# drake-1.net
KiCad netlist of a schematic drawn in Altium Designer
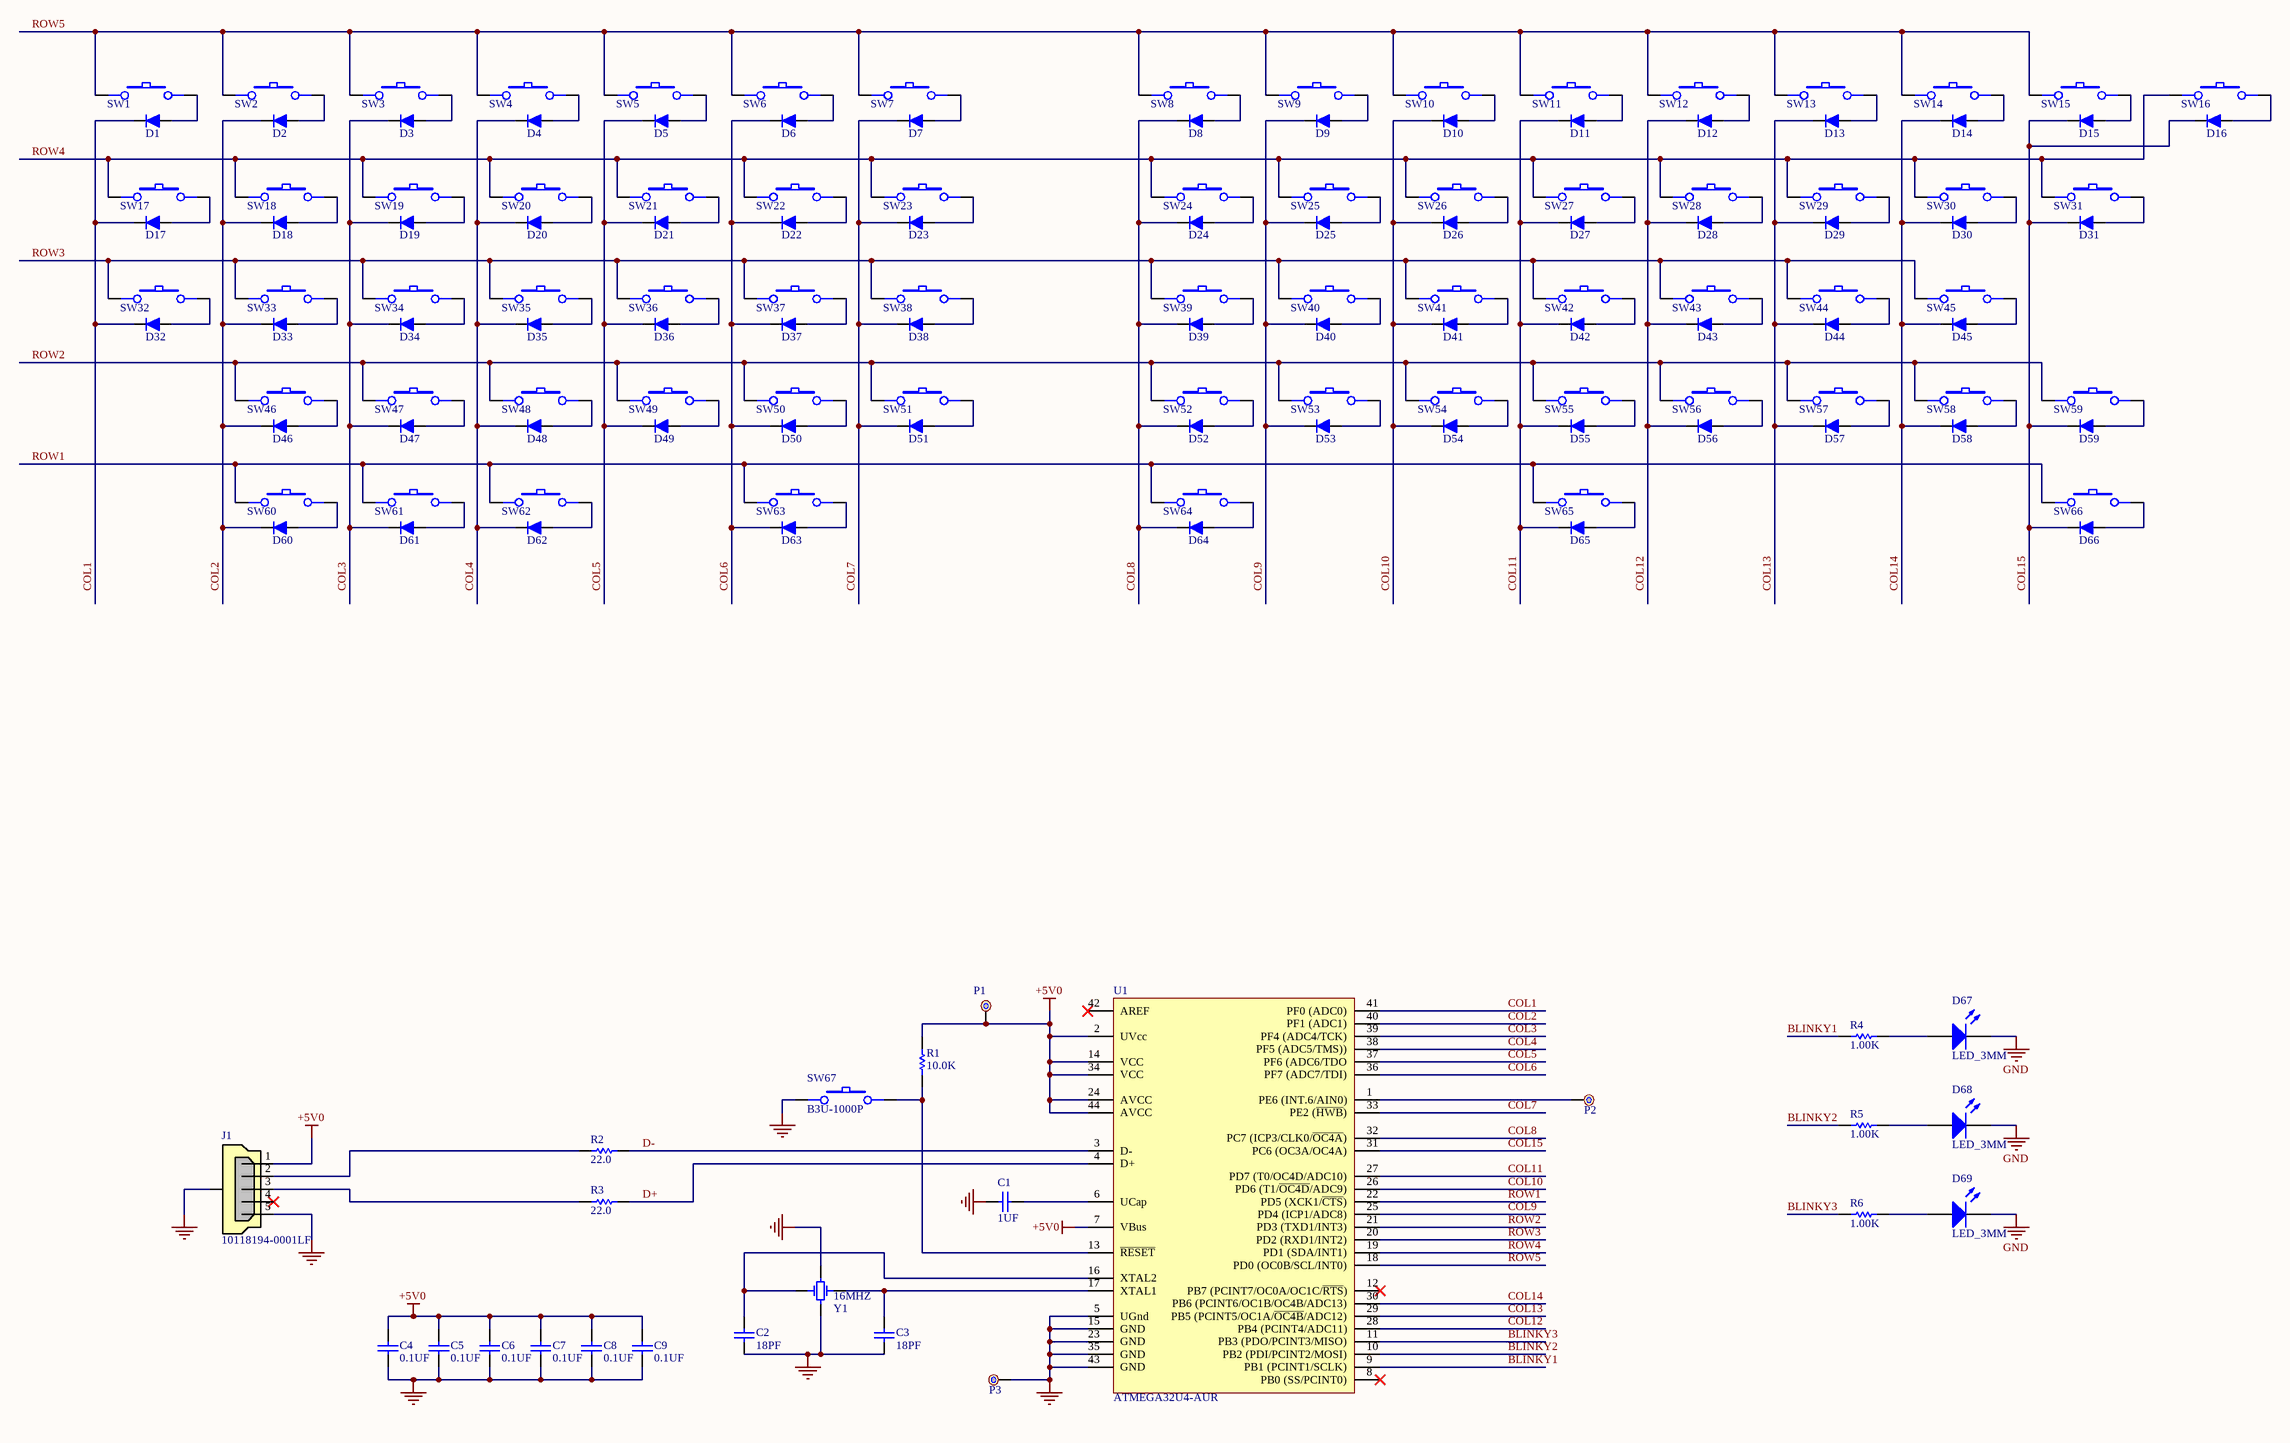
[diagram p0: drake-1.SchDoc]

(export (version "E")
  (design (tool "Eeschema 10.0.6"))
  (components
    (comp (ref "C1")
      (value "1UF")
      (footprint "CAPC2012X14N")
      (description "=Reference")
      (fields
        (field (name "MANUFACTURER") "Murata")
        (field (name "MANUFACTURER PART NUMBER") "GRM21BR71A105KA01L")
      )
      (libsource (lib "Altium_Library") (part "Capacitor-NP"))
    )
    (comp (ref "C2")
      (value "18PF")
      (footprint "CAPC1005X06N")
      (description "=Reference")
      (fields
        (field (name "MANUFACTURER") "Murata")
        (field (name "MANUFACTURER PART NUMBER") "GRM1555C1H180JA01D")
      )
      (libsource (lib "Altium_Library") (part "Capacitor-NP"))
    )
    (comp (ref "C3")
      (value "18PF")
      (footprint "CAPC1005X06N")
      (description "=Reference")
      (fields
        (field (name "MANUFACTURER") "Murata")
        (field (name "MANUFACTURER PART NUMBER") "GRM1555C1H180JA01D")
      )
      (libsource (lib "Altium_Library") (part "Capacitor-NP"))
    )
    (comp (ref "C4")
      (value "0.1UF")
      (footprint "CAPC1005X06N")
      (description "=Reference")
      (fields
        (field (name "MANUFACTURER") "Murata")
        (field (name "MANUFACTURER PART NUMBER") "GRM155R71C104KA88D")
      )
      (libsource (lib "Altium_Library") (part "Capacitor-NP"))
    )
    (comp (ref "C5")
      (value "0.1UF")
      (footprint "CAPC1005X06N")
      (description "=Reference")
      (fields
        (field (name "MANUFACTURER") "Murata")
        (field (name "MANUFACTURER PART NUMBER") "GRM155R71C104KA88D")
      )
      (libsource (lib "Altium_Library") (part "Capacitor-NP"))
    )
    (comp (ref "C6")
      (value "0.1UF")
      (footprint "CAPC1005X06N")
      (description "=Reference")
      (fields
        (field (name "MANUFACTURER") "Murata")
        (field (name "MANUFACTURER PART NUMBER") "GRM155R71C104KA88D")
      )
      (libsource (lib "Altium_Library") (part "Capacitor-NP"))
    )
    (comp (ref "C7")
      (value "0.1UF")
      (footprint "CAPC1005X06N")
      (description "=Reference")
      (fields
        (field (name "MANUFACTURER") "Murata")
        (field (name "MANUFACTURER PART NUMBER") "GRM155R71C104KA88D")
      )
      (libsource (lib "Altium_Library") (part "Capacitor-NP"))
    )
    (comp (ref "C8")
      (value "0.1UF")
      (footprint "CAPC1005X06N")
      (description "=Reference")
      (fields
        (field (name "MANUFACTURER") "Murata")
        (field (name "MANUFACTURER PART NUMBER") "GRM155R71C104KA88D")
      )
      (libsource (lib "Altium_Library") (part "Capacitor-NP"))
    )
    (comp (ref "C9")
      (value "0.1UF")
      (footprint "CAPC1005X06N")
      (description "=Reference")
      (fields
        (field (name "MANUFACTURER") "Murata")
        (field (name "MANUFACTURER PART NUMBER") "GRM155R71C104KA88D")
      )
      (libsource (lib "Altium_Library") (part "Capacitor-NP"))
    )
    (comp (ref "D1")
      (value "1N4148WS-7-F")
      (footprint "SOD-323")
      (description "DIODE GEN PURP 75V 150MA SOD323")
      (fields (field (name "MANUFACTURER") "Diodes Inc."))
      (libsource (lib "Schlib1") (part "1N4148WS-7-F"))
    )
    (comp (ref "D2")
      (value "1N4148WS-7-F")
      (footprint "SOD-323")
      (description "DIODE GEN PURP 75V 150MA SOD323")
      (fields (field (name "MANUFACTURER") "Diodes Inc."))
      (libsource (lib "Schlib1") (part "1N4148WS-7-F"))
    )
    (comp (ref "D3")
      (value "1N4148WS-7-F")
      (footprint "SOD-323")
      (description "DIODE GEN PURP 75V 150MA SOD323")
      (fields (field (name "MANUFACTURER") "Diodes Inc."))
      (libsource (lib "Schlib1") (part "1N4148WS-7-F"))
    )
    (comp (ref "D4")
      (value "1N4148WS-7-F")
      (footprint "SOD-323")
      (description "DIODE GEN PURP 75V 150MA SOD323")
      (fields (field (name "MANUFACTURER") "Diodes Inc."))
      (libsource (lib "Schlib1") (part "1N4148WS-7-F"))
    )
    (comp (ref "D5")
      (value "1N4148WS-7-F")
      (footprint "SOD-323")
      (description "DIODE GEN PURP 75V 150MA SOD323")
      (fields (field (name "MANUFACTURER") "Diodes Inc."))
      (libsource (lib "Schlib1") (part "1N4148WS-7-F"))
    )
    (comp (ref "D6")
      (value "1N4148WS-7-F")
      (footprint "SOD-323")
      (description "DIODE GEN PURP 75V 150MA SOD323")
      (fields (field (name "MANUFACTURER") "Diodes Inc."))
      (libsource (lib "Schlib1") (part "1N4148WS-7-F"))
    )
    (comp (ref "D7")
      (value "1N4148WS-7-F")
      (footprint "SOD-323")
      (description "DIODE GEN PURP 75V 150MA SOD323")
      (fields (field (name "MANUFACTURER") "Diodes Inc."))
      (libsource (lib "Schlib1") (part "1N4148WS-7-F"))
    )
    (comp (ref "D8")
      (value "1N4148WS-7-F")
      (footprint "SOD-323")
      (description "DIODE GEN PURP 75V 150MA SOD323")
      (fields (field (name "MANUFACTURER") "Diodes Inc."))
      (libsource (lib "Schlib1") (part "1N4148WS-7-F"))
    )
    (comp (ref "D9")
      (value "1N4148WS-7-F")
      (footprint "SOD-323")
      (description "DIODE GEN PURP 75V 150MA SOD323")
      (fields (field (name "MANUFACTURER") "Diodes Inc."))
      (libsource (lib "Schlib1") (part "1N4148WS-7-F"))
    )
    (comp (ref "D10")
      (value "1N4148WS-7-F")
      (footprint "SOD-323")
      (description "DIODE GEN PURP 75V 150MA SOD323")
      (fields (field (name "MANUFACTURER") "Diodes Inc."))
      (libsource (lib "Schlib1") (part "1N4148WS-7-F"))
    )
    (comp (ref "D11")
      (value "1N4148WS-7-F")
      (footprint "SOD-323")
      (description "DIODE GEN PURP 75V 150MA SOD323")
      (fields (field (name "MANUFACTURER") "Diodes Inc."))
      (libsource (lib "Schlib1") (part "1N4148WS-7-F"))
    )
    (comp (ref "D12")
      (value "1N4148WS-7-F")
      (footprint "SOD-323")
      (description "DIODE GEN PURP 75V 150MA SOD323")
      (fields (field (name "MANUFACTURER") "Diodes Inc."))
      (libsource (lib "Schlib1") (part "1N4148WS-7-F"))
    )
    (comp (ref "D13")
      (value "1N4148WS-7-F")
      (footprint "SOD-323")
      (description "DIODE GEN PURP 75V 150MA SOD323")
      (fields (field (name "MANUFACTURER") "Diodes Inc."))
      (libsource (lib "Schlib1") (part "1N4148WS-7-F"))
    )
    (comp (ref "D14")
      (value "1N4148WS-7-F")
      (footprint "SOD-323")
      (description "DIODE GEN PURP 75V 150MA SOD323")
      (fields (field (name "MANUFACTURER") "Diodes Inc."))
      (libsource (lib "Schlib1") (part "1N4148WS-7-F"))
    )
    (comp (ref "D15")
      (value "1N4148WS-7-F")
      (footprint "SOD-323")
      (description "DIODE GEN PURP 75V 150MA SOD323")
      (fields (field (name "MANUFACTURER") "Diodes Inc."))
      (libsource (lib "Schlib1") (part "1N4148WS-7-F"))
    )
    (comp (ref "D16")
      (value "1N4148WS-7-F")
      (footprint "SOD-323")
      (description "DIODE GEN PURP 75V 150MA SOD323")
      (fields (field (name "MANUFACTURER") "Diodes Inc."))
      (libsource (lib "Schlib1") (part "1N4148WS-7-F"))
    )
    (comp (ref "D17")
      (value "1N4148WS-7-F")
      (footprint "SOD-323")
      (description "DIODE GEN PURP 75V 150MA SOD323")
      (fields (field (name "MANUFACTURER") "Diodes Inc."))
      (libsource (lib "Schlib1") (part "1N4148WS-7-F"))
    )
    (comp (ref "D18")
      (value "1N4148WS-7-F")
      (footprint "SOD-323")
      (description "DIODE GEN PURP 75V 150MA SOD323")
      (fields (field (name "MANUFACTURER") "Diodes Inc."))
      (libsource (lib "Schlib1") (part "1N4148WS-7-F"))
    )
    (comp (ref "D19")
      (value "1N4148WS-7-F")
      (footprint "SOD-323")
      (description "DIODE GEN PURP 75V 150MA SOD323")
      (fields (field (name "MANUFACTURER") "Diodes Inc."))
      (libsource (lib "Schlib1") (part "1N4148WS-7-F"))
    )
    (comp (ref "D20")
      (value "1N4148WS-7-F")
      (footprint "SOD-323")
      (description "DIODE GEN PURP 75V 150MA SOD323")
      (fields (field (name "MANUFACTURER") "Diodes Inc."))
      (libsource (lib "Schlib1") (part "1N4148WS-7-F"))
    )
    (comp (ref "D21")
      (value "1N4148WS-7-F")
      (footprint "SOD-323")
      (description "DIODE GEN PURP 75V 150MA SOD323")
      (fields (field (name "MANUFACTURER") "Diodes Inc."))
      (libsource (lib "Schlib1") (part "1N4148WS-7-F"))
    )
    (comp (ref "D22")
      (value "1N4148WS-7-F")
      (footprint "SOD-323")
      (description "DIODE GEN PURP 75V 150MA SOD323")
      (fields (field (name "MANUFACTURER") "Diodes Inc."))
      (libsource (lib "Schlib1") (part "1N4148WS-7-F"))
    )
    (comp (ref "D23")
      (value "1N4148WS-7-F")
      (footprint "SOD-323")
      (description "DIODE GEN PURP 75V 150MA SOD323")
      (fields (field (name "MANUFACTURER") "Diodes Inc."))
      (libsource (lib "Schlib1") (part "1N4148WS-7-F"))
    )
    (comp (ref "D24")
      (value "1N4148WS-7-F")
      (footprint "SOD-323")
      (description "DIODE GEN PURP 75V 150MA SOD323")
      (fields (field (name "MANUFACTURER") "Diodes Inc."))
      (libsource (lib "Schlib1") (part "1N4148WS-7-F"))
    )
    (comp (ref "D25")
      (value "1N4148WS-7-F")
      (footprint "SOD-323")
      (description "DIODE GEN PURP 75V 150MA SOD323")
      (fields (field (name "MANUFACTURER") "Diodes Inc."))
      (libsource (lib "Schlib1") (part "1N4148WS-7-F"))
    )
    (comp (ref "D26")
      (value "1N4148WS-7-F")
      (footprint "SOD-323")
      (description "DIODE GEN PURP 75V 150MA SOD323")
      (fields (field (name "MANUFACTURER") "Diodes Inc."))
      (libsource (lib "Schlib1") (part "1N4148WS-7-F"))
    )
    (comp (ref "D27")
      (value "1N4148WS-7-F")
      (footprint "SOD-323")
      (description "DIODE GEN PURP 75V 150MA SOD323")
      (fields (field (name "MANUFACTURER") "Diodes Inc."))
      (libsource (lib "Schlib1") (part "1N4148WS-7-F"))
    )
    (comp (ref "D28")
      (value "1N4148WS-7-F")
      (footprint "SOD-323")
      (description "DIODE GEN PURP 75V 150MA SOD323")
      (fields (field (name "MANUFACTURER") "Diodes Inc."))
      (libsource (lib "Schlib1") (part "1N4148WS-7-F"))
    )
    (comp (ref "D29")
      (value "1N4148WS-7-F")
      (footprint "SOD-323")
      (description "DIODE GEN PURP 75V 150MA SOD323")
      (fields (field (name "MANUFACTURER") "Diodes Inc."))
      (libsource (lib "Schlib1") (part "1N4148WS-7-F"))
    )
    (comp (ref "D30")
      (value "1N4148WS-7-F")
      (footprint "SOD-323")
      (description "DIODE GEN PURP 75V 150MA SOD323")
      (fields (field (name "MANUFACTURER") "Diodes Inc."))
      (libsource (lib "Schlib1") (part "1N4148WS-7-F"))
    )
    (comp (ref "D31")
      (value "1N4148WS-7-F")
      (footprint "SOD-323")
      (description "DIODE GEN PURP 75V 150MA SOD323")
      (fields (field (name "MANUFACTURER") "Diodes Inc."))
      (libsource (lib "Schlib1") (part "1N4148WS-7-F"))
    )
    (comp (ref "D32")
      (value "1N4148WS-7-F")
      (footprint "SOD-323")
      (description "DIODE GEN PURP 75V 150MA SOD323")
      (fields (field (name "MANUFACTURER") "Diodes Inc."))
      (libsource (lib "Schlib1") (part "1N4148WS-7-F"))
    )
    (comp (ref "D33")
      (value "1N4148WS-7-F")
      (footprint "SOD-323")
      (description "DIODE GEN PURP 75V 150MA SOD323")
      (fields (field (name "MANUFACTURER") "Diodes Inc."))
      (libsource (lib "Schlib1") (part "1N4148WS-7-F"))
    )
    (comp (ref "D34")
      (value "1N4148WS-7-F")
      (footprint "SOD-323")
      (description "DIODE GEN PURP 75V 150MA SOD323")
      (fields (field (name "MANUFACTURER") "Diodes Inc."))
      (libsource (lib "Schlib1") (part "1N4148WS-7-F"))
    )
    (comp (ref "D35")
      (value "1N4148WS-7-F")
      (footprint "SOD-323")
      (description "DIODE GEN PURP 75V 150MA SOD323")
      (fields (field (name "MANUFACTURER") "Diodes Inc."))
      (libsource (lib "Schlib1") (part "1N4148WS-7-F"))
    )
    (comp (ref "D36")
      (value "1N4148WS-7-F")
      (footprint "SOD-323")
      (description "DIODE GEN PURP 75V 150MA SOD323")
      (fields (field (name "MANUFACTURER") "Diodes Inc."))
      (libsource (lib "Schlib1") (part "1N4148WS-7-F"))
    )
    (comp (ref "D37")
      (value "1N4148WS-7-F")
      (footprint "SOD-323")
      (description "DIODE GEN PURP 75V 150MA SOD323")
      (fields (field (name "MANUFACTURER") "Diodes Inc."))
      (libsource (lib "Schlib1") (part "1N4148WS-7-F"))
    )
    (comp (ref "D38")
      (value "1N4148WS-7-F")
      (footprint "SOD-323")
      (description "DIODE GEN PURP 75V 150MA SOD323")
      (fields (field (name "MANUFACTURER") "Diodes Inc."))
      (libsource (lib "Schlib1") (part "1N4148WS-7-F"))
    )
    (comp (ref "D39")
      (value "1N4148WS-7-F")
      (footprint "SOD-323")
      (description "DIODE GEN PURP 75V 150MA SOD323")
      (fields (field (name "MANUFACTURER") "Diodes Inc."))
      (libsource (lib "Schlib1") (part "1N4148WS-7-F"))
    )
    (comp (ref "D40")
      (value "1N4148WS-7-F")
      (footprint "SOD-323")
      (description "DIODE GEN PURP 75V 150MA SOD323")
      (fields (field (name "MANUFACTURER") "Diodes Inc."))
      (libsource (lib "Schlib1") (part "1N4148WS-7-F"))
    )
    (comp (ref "D41")
      (value "1N4148WS-7-F")
      (footprint "SOD-323")
      (description "DIODE GEN PURP 75V 150MA SOD323")
      (fields (field (name "MANUFACTURER") "Diodes Inc."))
      (libsource (lib "Schlib1") (part "1N4148WS-7-F"))
    )
    (comp (ref "D42")
      (value "1N4148WS-7-F")
      (footprint "SOD-323")
      (description "DIODE GEN PURP 75V 150MA SOD323")
      (fields (field (name "MANUFACTURER") "Diodes Inc."))
      (libsource (lib "Schlib1") (part "1N4148WS-7-F"))
    )
    (comp (ref "D43")
      (value "1N4148WS-7-F")
      (footprint "SOD-323")
      (description "DIODE GEN PURP 75V 150MA SOD323")
      (fields (field (name "MANUFACTURER") "Diodes Inc."))
      (libsource (lib "Schlib1") (part "1N4148WS-7-F"))
    )
    (comp (ref "D44")
      (value "1N4148WS-7-F")
      (footprint "SOD-323")
      (description "DIODE GEN PURP 75V 150MA SOD323")
      (fields (field (name "MANUFACTURER") "Diodes Inc."))
      (libsource (lib "Schlib1") (part "1N4148WS-7-F"))
    )
    (comp (ref "D45")
      (value "1N4148WS-7-F")
      (footprint "SOD-323")
      (description "DIODE GEN PURP 75V 150MA SOD323")
      (fields (field (name "MANUFACTURER") "Diodes Inc."))
      (libsource (lib "Schlib1") (part "1N4148WS-7-F"))
    )
    (comp (ref "D46")
      (value "1N4148WS-7-F")
      (footprint "SOD-323")
      (description "DIODE GEN PURP 75V 150MA SOD323")
      (fields (field (name "MANUFACTURER") "Diodes Inc."))
      (libsource (lib "Schlib1") (part "1N4148WS-7-F"))
    )
    (comp (ref "D47")
      (value "1N4148WS-7-F")
      (footprint "SOD-323")
      (description "DIODE GEN PURP 75V 150MA SOD323")
      (fields (field (name "MANUFACTURER") "Diodes Inc."))
      (libsource (lib "Schlib1") (part "1N4148WS-7-F"))
    )
    (comp (ref "D48")
      (value "1N4148WS-7-F")
      (footprint "SOD-323")
      (description "DIODE GEN PURP 75V 150MA SOD323")
      (fields (field (name "MANUFACTURER") "Diodes Inc."))
      (libsource (lib "Schlib1") (part "1N4148WS-7-F"))
    )
    (comp (ref "D49")
      (value "1N4148WS-7-F")
      (footprint "SOD-323")
      (description "DIODE GEN PURP 75V 150MA SOD323")
      (fields (field (name "MANUFACTURER") "Diodes Inc."))
      (libsource (lib "Schlib1") (part "1N4148WS-7-F"))
    )
    (comp (ref "D50")
      (value "1N4148WS-7-F")
      (footprint "SOD-323")
      (description "DIODE GEN PURP 75V 150MA SOD323")
      (fields (field (name "MANUFACTURER") "Diodes Inc."))
      (libsource (lib "Schlib1") (part "1N4148WS-7-F"))
    )
    (comp (ref "D51")
      (value "1N4148WS-7-F")
      (footprint "SOD-323")
      (description "DIODE GEN PURP 75V 150MA SOD323")
      (fields (field (name "MANUFACTURER") "Diodes Inc."))
      (libsource (lib "Schlib1") (part "1N4148WS-7-F"))
    )
    (comp (ref "D52")
      (value "1N4148WS-7-F")
      (footprint "SOD-323")
      (description "DIODE GEN PURP 75V 150MA SOD323")
      (fields (field (name "MANUFACTURER") "Diodes Inc."))
      (libsource (lib "Schlib1") (part "1N4148WS-7-F"))
    )
    (comp (ref "D53")
      (value "1N4148WS-7-F")
      (footprint "SOD-323")
      (description "DIODE GEN PURP 75V 150MA SOD323")
      (fields (field (name "MANUFACTURER") "Diodes Inc."))
      (libsource (lib "Schlib1") (part "1N4148WS-7-F"))
    )
    (comp (ref "D54")
      (value "1N4148WS-7-F")
      (footprint "SOD-323")
      (description "DIODE GEN PURP 75V 150MA SOD323")
      (fields (field (name "MANUFACTURER") "Diodes Inc."))
      (libsource (lib "Schlib1") (part "1N4148WS-7-F"))
    )
    (comp (ref "D55")
      (value "1N4148WS-7-F")
      (footprint "SOD-323")
      (description "DIODE GEN PURP 75V 150MA SOD323")
      (fields (field (name "MANUFACTURER") "Diodes Inc."))
      (libsource (lib "Schlib1") (part "1N4148WS-7-F"))
    )
    (comp (ref "D56")
      (value "1N4148WS-7-F")
      (footprint "SOD-323")
      (description "DIODE GEN PURP 75V 150MA SOD323")
      (fields (field (name "MANUFACTURER") "Diodes Inc."))
      (libsource (lib "Schlib1") (part "1N4148WS-7-F"))
    )
    (comp (ref "D57")
      (value "1N4148WS-7-F")
      (footprint "SOD-323")
      (description "DIODE GEN PURP 75V 150MA SOD323")
      (fields (field (name "MANUFACTURER") "Diodes Inc."))
      (libsource (lib "Schlib1") (part "1N4148WS-7-F"))
    )
    (comp (ref "D58")
      (value "1N4148WS-7-F")
      (footprint "SOD-323")
      (description "DIODE GEN PURP 75V 150MA SOD323")
      (fields (field (name "MANUFACTURER") "Diodes Inc."))
      (libsource (lib "Schlib1") (part "1N4148WS-7-F"))
    )
    (comp (ref "D59")
      (value "1N4148WS-7-F")
      (footprint "SOD-323")
      (description "DIODE GEN PURP 75V 150MA SOD323")
      (fields (field (name "MANUFACTURER") "Diodes Inc."))
      (libsource (lib "Schlib1") (part "1N4148WS-7-F"))
    )
    (comp (ref "D60")
      (value "1N4148WS-7-F")
      (footprint "SOD-323")
      (description "DIODE GEN PURP 75V 150MA SOD323")
      (fields (field (name "MANUFACTURER") "Diodes Inc."))
      (libsource (lib "Schlib1") (part "1N4148WS-7-F"))
    )
    (comp (ref "D61")
      (value "1N4148WS-7-F")
      (footprint "SOD-323")
      (description "DIODE GEN PURP 75V 150MA SOD323")
      (fields (field (name "MANUFACTURER") "Diodes Inc."))
      (libsource (lib "Schlib1") (part "1N4148WS-7-F"))
    )
    (comp (ref "D62")
      (value "1N4148WS-7-F")
      (footprint "SOD-323")
      (description "DIODE GEN PURP 75V 150MA SOD323")
      (fields (field (name "MANUFACTURER") "Diodes Inc."))
      (libsource (lib "Schlib1") (part "1N4148WS-7-F"))
    )
    (comp (ref "D63")
      (value "1N4148WS-7-F")
      (footprint "SOD-323")
      (description "DIODE GEN PURP 75V 150MA SOD323")
      (fields (field (name "MANUFACTURER") "Diodes Inc."))
      (libsource (lib "Schlib1") (part "1N4148WS-7-F"))
    )
    (comp (ref "D64")
      (value "1N4148WS-7-F")
      (footprint "SOD-323")
      (description "DIODE GEN PURP 75V 150MA SOD323")
      (fields (field (name "MANUFACTURER") "Diodes Inc."))
      (libsource (lib "Schlib1") (part "1N4148WS-7-F"))
    )
    (comp (ref "D65")
      (value "1N4148WS-7-F")
      (footprint "SOD-323")
      (description "DIODE GEN PURP 75V 150MA SOD323")
      (fields (field (name "MANUFACTURER") "Diodes Inc."))
      (libsource (lib "Schlib1") (part "1N4148WS-7-F"))
    )
    (comp (ref "D66")
      (value "1N4148WS-7-F")
      (footprint "SOD-323")
      (description "DIODE GEN PURP 75V 150MA SOD323")
      (fields (field (name "MANUFACTURER") "Diodes Inc."))
      (libsource (lib "Schlib1") (part "1N4148WS-7-F"))
    )
    (comp (ref "D67")
      (value "LED_3MM")
      (footprint "LED T-1 3mm - straight")
      (description "LED 3MM")
      (libsource (lib "Schlib1") (part "LED_3MM"))
    )
    (comp (ref "D68")
      (value "LED_3MM")
      (footprint "LED T-1 3mm - straight")
      (description "LED 3MM")
      (libsource (lib "Schlib1") (part "LED_3MM"))
    )
    (comp (ref "D69")
      (value "LED_3MM")
      (footprint "LED T-1 3mm - straight")
      (description "LED 3MM")
      (libsource (lib "Schlib1") (part "LED_3MM"))
    )
    (comp (ref "J1")
      (value "10118194-0001LF")
      (footprint "USB Micro 10118194")
      (description "USB - micro B")
      (fields (field (name "MANUFACTURER") "Amphenol FCI"))
      (libsource (lib "Schlib1") (part "USB Micro 10118194-0001LF"))
    )
    (comp (ref "P1")
      (value "90MIL")
      (footprint "Pad_90mil_drill_55mil")
      (description "=Reference")
      (libsource (lib "Altium_Library") (part "Wire_Hole"))
    )
    (comp (ref "P2")
      (value "90MIL")
      (footprint "Pad_90mil_drill_55mil")
      (description "=Reference")
      (libsource (lib "Altium_Library") (part "Wire_Hole"))
    )
    (comp (ref "P3")
      (value "90MIL")
      (footprint "Pad_90mil_drill_55mil")
      (description "=Reference")
      (libsource (lib "Altium_Library") (part "Wire_Hole"))
    )
    (comp (ref "R1")
      (value "10.0K")
      (footprint "RESC1005X04N")
      (description "=Reference")
      (fields
        (field (name "MANUFACTURER") "Vishay")
        (field (name "MANUFACTURER PART NUMBER") "CRCW040210K0FKED")
      )
      (libsource (lib "Altium_Library") (part "Resistor"))
    )
    (comp (ref "R2")
      (value "22.0")
      (footprint "RESC1005X04N")
      (description "=Reference")
      (fields
        (field (name "MANUFACTURER") "Vishay")
        (field (name "MANUFACTURER PART NUMBER") "CRCW040222R0FKED")
      )
      (libsource (lib "Altium_Library") (part "Resistor"))
    )
    (comp (ref "R3")
      (value "22.0")
      (footprint "RESC1005X04N")
      (description "=Reference")
      (fields
        (field (name "MANUFACTURER") "Vishay")
        (field (name "MANUFACTURER PART NUMBER") "CRCW040222R0FKED")
      )
      (libsource (lib "Altium_Library") (part "Resistor"))
    )
    (comp (ref "R4")
      (value "1.00K")
      (footprint "RESC1005X04N")
      (description "=Reference")
      (fields
        (field (name "MANUFACTURER") "Vishay")
        (field (name "MANUFACTURER PART NUMBER") "CRCW04021K00FKEDC")
      )
      (libsource (lib "Altium_Library") (part "Resistor"))
    )
    (comp (ref "R5")
      (value "1.00K")
      (footprint "RESC1005X04N")
      (description "=Reference")
      (fields
        (field (name "MANUFACTURER") "Vishay")
        (field (name "MANUFACTURER PART NUMBER") "CRCW04021K00FKEDC")
      )
      (libsource (lib "Altium_Library") (part "Resistor"))
    )
    (comp (ref "R6")
      (value "1.00K")
      (footprint "RESC1005X04N")
      (description "=Reference")
      (fields
        (field (name "MANUFACTURER") "Vishay")
        (field (name "MANUFACTURER PART NUMBER") "CRCW04021K00FKEDC")
      )
      (libsource (lib "Altium_Library") (part "Resistor"))
    )
    (comp (ref "SW1")
      (value "MX1A-11NW")
      (footprint "SW-MX1A-11NW")
      (description "SWITCH PUSH SPST-NO 0.01A 12V")
      (fields (field (name "MANUFACTURER") "Cherry"))
      (libsource (lib "Schlib1") (part "SW-CHERRY-MX"))
    )
    (comp (ref "SW2")
      (value "MX1A-11NW")
      (footprint "SW-MX1A-11NW")
      (description "SWITCH PUSH SPST-NO 0.01A 12V")
      (fields (field (name "MANUFACTURER") "Cherry"))
      (libsource (lib "Schlib1") (part "SW-CHERRY-MX"))
    )
    (comp (ref "SW3")
      (value "MX1A-11NW")
      (footprint "SW-MX1A-11NW")
      (description "SWITCH PUSH SPST-NO 0.01A 12V")
      (fields (field (name "MANUFACTURER") "Cherry"))
      (libsource (lib "Schlib1") (part "SW-CHERRY-MX"))
    )
    (comp (ref "SW4")
      (value "MX1A-11NW")
      (footprint "SW-MX1A-11NW")
      (description "SWITCH PUSH SPST-NO 0.01A 12V")
      (fields (field (name "MANUFACTURER") "Cherry"))
      (libsource (lib "Schlib1") (part "SW-CHERRY-MX"))
    )
    (comp (ref "SW5")
      (value "MX1A-11NW")
      (footprint "SW-MX1A-11NW")
      (description "SWITCH PUSH SPST-NO 0.01A 12V")
      (fields (field (name "MANUFACTURER") "Cherry"))
      (libsource (lib "Schlib1") (part "SW-CHERRY-MX"))
    )
    (comp (ref "SW6")
      (value "MX1A-11NW")
      (footprint "SW-MX1A-11NW")
      (description "SWITCH PUSH SPST-NO 0.01A 12V")
      (fields (field (name "MANUFACTURER") "Cherry"))
      (libsource (lib "Schlib1") (part "SW-CHERRY-MX"))
    )
    (comp (ref "SW7")
      (value "MX1A-11NW")
      (footprint "SW-MX1A-11NW")
      (description "SWITCH PUSH SPST-NO 0.01A 12V")
      (fields (field (name "MANUFACTURER") "Cherry"))
      (libsource (lib "Schlib1") (part "SW-CHERRY-MX"))
    )
    (comp (ref "SW8")
      (value "MX1A-11NW")
      (footprint "SW-MX1A-11NW")
      (description "SWITCH PUSH SPST-NO 0.01A 12V")
      (fields (field (name "MANUFACTURER") "Cherry"))
      (libsource (lib "Schlib1") (part "SW-CHERRY-MX"))
    )
    (comp (ref "SW9")
      (value "MX1A-11NW")
      (footprint "SW-MX1A-11NW")
      (description "SWITCH PUSH SPST-NO 0.01A 12V")
      (fields (field (name "MANUFACTURER") "Cherry"))
      (libsource (lib "Schlib1") (part "SW-CHERRY-MX"))
    )
    (comp (ref "SW10")
      (value "MX1A-11NW")
      (footprint "SW-MX1A-11NW")
      (description "SWITCH PUSH SPST-NO 0.01A 12V")
      (fields (field (name "MANUFACTURER") "Cherry"))
      (libsource (lib "Schlib1") (part "SW-CHERRY-MX"))
    )
    (comp (ref "SW11")
      (value "MX1A-11NW")
      (footprint "SW-MX1A-11NW")
      (description "SWITCH PUSH SPST-NO 0.01A 12V")
      (fields (field (name "MANUFACTURER") "Cherry"))
      (libsource (lib "Schlib1") (part "SW-CHERRY-MX"))
    )
    (comp (ref "SW12")
      (value "MX1A-11NW")
      (footprint "SW-MX1A-11NW")
      (description "SWITCH PUSH SPST-NO 0.01A 12V")
      (fields (field (name "MANUFACTURER") "Cherry"))
      (libsource (lib "Schlib1") (part "SW-CHERRY-MX"))
    )
    (comp (ref "SW13")
      (value "MX1A-11NW")
      (footprint "SW-MX1A-11NW")
      (description "SWITCH PUSH SPST-NO 0.01A 12V")
      (fields (field (name "MANUFACTURER") "Cherry"))
      (libsource (lib "Schlib1") (part "SW-CHERRY-MX"))
    )
    (comp (ref "SW14")
      (value "MX1A-11NW")
      (footprint "SW-MX1A-11NW")
      (description "SWITCH PUSH SPST-NO 0.01A 12V")
      (fields (field (name "MANUFACTURER") "Cherry"))
      (libsource (lib "Schlib1") (part "SW-CHERRY-MX"))
    )
    (comp (ref "SW15")
      (value "MX1A-11NW")
      (footprint "SW-MX1A-11NW")
      (description "SWITCH PUSH SPST-NO 0.01A 12V")
      (fields (field (name "MANUFACTURER") "Cherry"))
      (libsource (lib "Schlib1") (part "SW-CHERRY-MX"))
    )
    (comp (ref "SW16")
      (value "MX1A-11NW")
      (footprint "SW-MX1A-11NW")
      (description "SWITCH PUSH SPST-NO 0.01A 12V")
      (fields (field (name "MANUFACTURER") "Cherry"))
      (libsource (lib "Schlib1") (part "SW-CHERRY-MX"))
    )
    (comp (ref "SW17")
      (value "MX1A-11NW")
      (footprint "SW-MX1A-11NW")
      (description "SWITCH PUSH SPST-NO 0.01A 12V")
      (fields (field (name "MANUFACTURER") "Cherry"))
      (libsource (lib "Schlib1") (part "SW-CHERRY-MX"))
    )
    (comp (ref "SW18")
      (value "MX1A-11NW")
      (footprint "SW-MX1A-11NW")
      (description "SWITCH PUSH SPST-NO 0.01A 12V")
      (fields (field (name "MANUFACTURER") "Cherry"))
      (libsource (lib "Schlib1") (part "SW-CHERRY-MX"))
    )
    (comp (ref "SW19")
      (value "MX1A-11NW")
      (footprint "SW-MX1A-11NW")
      (description "SWITCH PUSH SPST-NO 0.01A 12V")
      (fields (field (name "MANUFACTURER") "Cherry"))
      (libsource (lib "Schlib1") (part "SW-CHERRY-MX"))
    )
    (comp (ref "SW20")
      (value "MX1A-11NW")
      (footprint "SW-MX1A-11NW")
      (description "SWITCH PUSH SPST-NO 0.01A 12V")
      (fields (field (name "MANUFACTURER") "Cherry"))
      (libsource (lib "Schlib1") (part "SW-CHERRY-MX"))
    )
    (comp (ref "SW21")
      (value "MX1A-11NW")
      (footprint "SW-MX1A-11NW")
      (description "SWITCH PUSH SPST-NO 0.01A 12V")
      (fields (field (name "MANUFACTURER") "Cherry"))
      (libsource (lib "Schlib1") (part "SW-CHERRY-MX"))
    )
    (comp (ref "SW22")
      (value "MX1A-11NW")
      (footprint "SW-MX1A-11NW")
      (description "SWITCH PUSH SPST-NO 0.01A 12V")
      (fields (field (name "MANUFACTURER") "Cherry"))
      (libsource (lib "Schlib1") (part "SW-CHERRY-MX"))
    )
    (comp (ref "SW23")
      (value "MX1A-11NW")
      (footprint "SW-MX1A-11NW")
      (description "SWITCH PUSH SPST-NO 0.01A 12V")
      (fields (field (name "MANUFACTURER") "Cherry"))
      (libsource (lib "Schlib1") (part "SW-CHERRY-MX"))
    )
    (comp (ref "SW24")
      (value "MX1A-11NW")
      (footprint "SW-MX1A-11NW")
      (description "SWITCH PUSH SPST-NO 0.01A 12V")
      (fields (field (name "MANUFACTURER") "Cherry"))
      (libsource (lib "Schlib1") (part "SW-CHERRY-MX"))
    )
    (comp (ref "SW25")
      (value "MX1A-11NW")
      (footprint "SW-MX1A-11NW")
      (description "SWITCH PUSH SPST-NO 0.01A 12V")
      (fields (field (name "MANUFACTURER") "Cherry"))
      (libsource (lib "Schlib1") (part "SW-CHERRY-MX"))
    )
    (comp (ref "SW26")
      (value "MX1A-11NW")
      (footprint "SW-MX1A-11NW")
      (description "SWITCH PUSH SPST-NO 0.01A 12V")
      (fields (field (name "MANUFACTURER") "Cherry"))
      (libsource (lib "Schlib1") (part "SW-CHERRY-MX"))
    )
    (comp (ref "SW27")
      (value "MX1A-11NW")
      (footprint "SW-MX1A-11NW")
      (description "SWITCH PUSH SPST-NO 0.01A 12V")
      (fields (field (name "MANUFACTURER") "Cherry"))
      (libsource (lib "Schlib1") (part "SW-CHERRY-MX"))
    )
    (comp (ref "SW28")
      (value "MX1A-11NW")
      (footprint "SW-MX1A-11NW")
      (description "SWITCH PUSH SPST-NO 0.01A 12V")
      (fields (field (name "MANUFACTURER") "Cherry"))
      (libsource (lib "Schlib1") (part "SW-CHERRY-MX"))
    )
    (comp (ref "SW29")
      (value "MX1A-11NW")
      (footprint "SW-MX1A-11NW")
      (description "SWITCH PUSH SPST-NO 0.01A 12V")
      (fields (field (name "MANUFACTURER") "Cherry"))
      (libsource (lib "Schlib1") (part "SW-CHERRY-MX"))
    )
    (comp (ref "SW30")
      (value "MX1A-11NW")
      (footprint "SW-MX1A-11NW")
      (description "SWITCH PUSH SPST-NO 0.01A 12V")
      (fields (field (name "MANUFACTURER") "Cherry"))
      (libsource (lib "Schlib1") (part "SW-CHERRY-MX"))
    )
    (comp (ref "SW31")
      (value "MX1A-11NW")
      (footprint "SW-MX1A-11NW")
      (description "SWITCH PUSH SPST-NO 0.01A 12V")
      (fields (field (name "MANUFACTURER") "Cherry"))
      (libsource (lib "Schlib1") (part "SW-CHERRY-MX"))
    )
    (comp (ref "SW32")
      (value "MX1A-11NW")
      (footprint "SW-MX1A-11NW")
      (description "SWITCH PUSH SPST-NO 0.01A 12V")
      (fields (field (name "MANUFACTURER") "Cherry"))
      (libsource (lib "Schlib1") (part "SW-CHERRY-MX"))
    )
    (comp (ref "SW33")
      (value "MX1A-11NW")
      (footprint "SW-MX1A-11NW")
      (description "SWITCH PUSH SPST-NO 0.01A 12V")
      (fields (field (name "MANUFACTURER") "Cherry"))
      (libsource (lib "Schlib1") (part "SW-CHERRY-MX"))
    )
    (comp (ref "SW34")
      (value "MX1A-11NW")
      (footprint "SW-MX1A-11NW")
      (description "SWITCH PUSH SPST-NO 0.01A 12V")
      (fields (field (name "MANUFACTURER") "Cherry"))
      (libsource (lib "Schlib1") (part "SW-CHERRY-MX"))
    )
    (comp (ref "SW35")
      (value "MX1A-11NW")
      (footprint "SW-MX1A-11NW")
      (description "SWITCH PUSH SPST-NO 0.01A 12V")
      (fields (field (name "MANUFACTURER") "Cherry"))
      (libsource (lib "Schlib1") (part "SW-CHERRY-MX"))
    )
    (comp (ref "SW36")
      (value "MX1A-11NW")
      (footprint "SW-MX1A-11NW")
      (description "SWITCH PUSH SPST-NO 0.01A 12V")
      (fields (field (name "MANUFACTURER") "Cherry"))
      (libsource (lib "Schlib1") (part "SW-CHERRY-MX"))
    )
    (comp (ref "SW37")
      (value "MX1A-11NW")
      (footprint "SW-MX1A-11NW")
      (description "SWITCH PUSH SPST-NO 0.01A 12V")
      (fields (field (name "MANUFACTURER") "Cherry"))
      (libsource (lib "Schlib1") (part "SW-CHERRY-MX"))
    )
    (comp (ref "SW38")
      (value "MX1A-11NW")
      (footprint "SW-MX1A-11NW")
      (description "SWITCH PUSH SPST-NO 0.01A 12V")
      (fields (field (name "MANUFACTURER") "Cherry"))
      (libsource (lib "Schlib1") (part "SW-CHERRY-MX"))
    )
    (comp (ref "SW39")
      (value "MX1A-11NW")
      (footprint "SW-MX1A-11NW")
      (description "SWITCH PUSH SPST-NO 0.01A 12V")
      (fields (field (name "MANUFACTURER") "Cherry"))
      (libsource (lib "Schlib1") (part "SW-CHERRY-MX"))
    )
    (comp (ref "SW40")
      (value "MX1A-11NW")
      (footprint "SW-MX1A-11NW")
      (description "SWITCH PUSH SPST-NO 0.01A 12V")
      (fields (field (name "MANUFACTURER") "Cherry"))
      (libsource (lib "Schlib1") (part "SW-CHERRY-MX"))
    )
    (comp (ref "SW41")
      (value "MX1A-11NW")
      (footprint "SW-MX1A-11NW")
      (description "SWITCH PUSH SPST-NO 0.01A 12V")
      (fields (field (name "MANUFACTURER") "Cherry"))
      (libsource (lib "Schlib1") (part "SW-CHERRY-MX"))
    )
    (comp (ref "SW42")
      (value "MX1A-11NW")
      (footprint "SW-MX1A-11NW")
      (description "SWITCH PUSH SPST-NO 0.01A 12V")
      (fields (field (name "MANUFACTURER") "Cherry"))
      (libsource (lib "Schlib1") (part "SW-CHERRY-MX"))
    )
    (comp (ref "SW43")
      (value "MX1A-11NW")
      (footprint "SW-MX1A-11NW")
      (description "SWITCH PUSH SPST-NO 0.01A 12V")
      (fields (field (name "MANUFACTURER") "Cherry"))
      (libsource (lib "Schlib1") (part "SW-CHERRY-MX"))
    )
    (comp (ref "SW44")
      (value "MX1A-11NW")
      (footprint "SW-MX1A-11NW")
      (description "SWITCH PUSH SPST-NO 0.01A 12V")
      (fields (field (name "MANUFACTURER") "Cherry"))
      (libsource (lib "Schlib1") (part "SW-CHERRY-MX"))
    )
    (comp (ref "SW45")
      (value "MX1A-11NW")
      (footprint "SW-MX1A-11NW")
      (description "SWITCH PUSH SPST-NO 0.01A 12V")
      (fields (field (name "MANUFACTURER") "Cherry"))
      (libsource (lib "Schlib1") (part "SW-CHERRY-MX"))
    )
    (comp (ref "SW46")
      (value "MX1A-11NW")
      (footprint "SW-MX1A-11NW")
      (description "SWITCH PUSH SPST-NO 0.01A 12V")
      (fields (field (name "MANUFACTURER") "Cherry"))
      (libsource (lib "Schlib1") (part "SW-CHERRY-MX"))
    )
    (comp (ref "SW47")
      (value "MX1A-11NW")
      (footprint "SW-MX1A-11NW")
      (description "SWITCH PUSH SPST-NO 0.01A 12V")
      (fields (field (name "MANUFACTURER") "Cherry"))
      (libsource (lib "Schlib1") (part "SW-CHERRY-MX"))
    )
    (comp (ref "SW48")
      (value "MX1A-11NW")
      (footprint "SW-MX1A-11NW")
      (description "SWITCH PUSH SPST-NO 0.01A 12V")
      (fields (field (name "MANUFACTURER") "Cherry"))
      (libsource (lib "Schlib1") (part "SW-CHERRY-MX"))
    )
    (comp (ref "SW49")
      (value "MX1A-11NW")
      (footprint "SW-MX1A-11NW")
      (description "SWITCH PUSH SPST-NO 0.01A 12V")
      (fields (field (name "MANUFACTURER") "Cherry"))
      (libsource (lib "Schlib1") (part "SW-CHERRY-MX"))
    )
    (comp (ref "SW50")
      (value "MX1A-11NW")
      (footprint "SW-MX1A-11NW")
      (description "SWITCH PUSH SPST-NO 0.01A 12V")
      (fields (field (name "MANUFACTURER") "Cherry"))
      (libsource (lib "Schlib1") (part "SW-CHERRY-MX"))
    )
    (comp (ref "SW51")
      (value "MX1A-11NW")
      (footprint "SW-MX1A-11NW")
      (description "SWITCH PUSH SPST-NO 0.01A 12V")
      (fields (field (name "MANUFACTURER") "Cherry"))
      (libsource (lib "Schlib1") (part "SW-CHERRY-MX"))
    )
    (comp (ref "SW52")
      (value "MX1A-11NW")
      (footprint "SW-MX1A-11NW")
      (description "SWITCH PUSH SPST-NO 0.01A 12V")
      (fields (field (name "MANUFACTURER") "Cherry"))
      (libsource (lib "Schlib1") (part "SW-CHERRY-MX"))
    )
    (comp (ref "SW53")
      (value "MX1A-11NW")
      (footprint "SW-MX1A-11NW")
      (description "SWITCH PUSH SPST-NO 0.01A 12V")
      (fields (field (name "MANUFACTURER") "Cherry"))
      (libsource (lib "Schlib1") (part "SW-CHERRY-MX"))
    )
    (comp (ref "SW54")
      (value "MX1A-11NW")
      (footprint "SW-MX1A-11NW")
      (description "SWITCH PUSH SPST-NO 0.01A 12V")
      (fields (field (name "MANUFACTURER") "Cherry"))
      (libsource (lib "Schlib1") (part "SW-CHERRY-MX"))
    )
    (comp (ref "SW55")
      (value "MX1A-11NW")
      (footprint "SW-MX1A-11NW")
      (description "SWITCH PUSH SPST-NO 0.01A 12V")
      (fields (field (name "MANUFACTURER") "Cherry"))
      (libsource (lib "Schlib1") (part "SW-CHERRY-MX"))
    )
    (comp (ref "SW56")
      (value "MX1A-11NW")
      (footprint "SW-MX1A-11NW")
      (description "SWITCH PUSH SPST-NO 0.01A 12V")
      (fields (field (name "MANUFACTURER") "Cherry"))
      (libsource (lib "Schlib1") (part "SW-CHERRY-MX"))
    )
    (comp (ref "SW57")
      (value "MX1A-11NW")
      (footprint "SW-MX1A-11NW")
      (description "SWITCH PUSH SPST-NO 0.01A 12V")
      (fields (field (name "MANUFACTURER") "Cherry"))
      (libsource (lib "Schlib1") (part "SW-CHERRY-MX"))
    )
    (comp (ref "SW58")
      (value "MX1A-11NW")
      (footprint "SW-MX1A-11NW")
      (description "SWITCH PUSH SPST-NO 0.01A 12V")
      (fields (field (name "MANUFACTURER") "Cherry"))
      (libsource (lib "Schlib1") (part "SW-CHERRY-MX"))
    )
    (comp (ref "SW59")
      (value "MX1A-11NW")
      (footprint "SW-MX1A-11NW")
      (description "SWITCH PUSH SPST-NO 0.01A 12V")
      (fields (field (name "MANUFACTURER") "Cherry"))
      (libsource (lib "Schlib1") (part "SW-CHERRY-MX"))
    )
    (comp (ref "SW60")
      (value "MX1A-11NW")
      (footprint "SW-MX1A-11NW")
      (description "SWITCH PUSH SPST-NO 0.01A 12V")
      (fields (field (name "MANUFACTURER") "Cherry"))
      (libsource (lib "Schlib1") (part "SW-CHERRY-MX"))
    )
    (comp (ref "SW61")
      (value "MX1A-11NW")
      (footprint "SW-MX1A-11NW")
      (description "SWITCH PUSH SPST-NO 0.01A 12V")
      (fields (field (name "MANUFACTURER") "Cherry"))
      (libsource (lib "Schlib1") (part "SW-CHERRY-MX"))
    )
    (comp (ref "SW62")
      (value "MX1A-11NW")
      (footprint "SW-MX1A-11NW")
      (description "SWITCH PUSH SPST-NO 0.01A 12V")
      (fields (field (name "MANUFACTURER") "Cherry"))
      (libsource (lib "Schlib1") (part "SW-CHERRY-MX"))
    )
    (comp (ref "SW63")
      (value "MX1A-11NW")
      (footprint "SW-MX1A-11NW")
      (description "SWITCH PUSH SPST-NO 0.01A 12V")
      (fields (field (name "MANUFACTURER") "Cherry"))
      (libsource (lib "Schlib1") (part "SW-CHERRY-MX"))
    )
    (comp (ref "SW64")
      (value "MX1A-11NW")
      (footprint "SW-MX1A-11NW")
      (description "SWITCH PUSH SPST-NO 0.01A 12V")
      (fields (field (name "MANUFACTURER") "Cherry"))
      (libsource (lib "Schlib1") (part "SW-CHERRY-MX"))
    )
    (comp (ref "SW65")
      (value "MX1A-11NW")
      (footprint "SW-MX1A-11NW")
      (description "SWITCH PUSH SPST-NO 0.01A 12V")
      (fields (field (name "MANUFACTURER") "Cherry"))
      (libsource (lib "Schlib1") (part "SW-CHERRY-MX"))
    )
    (comp (ref "SW66")
      (value "MX1A-11NW")
      (footprint "SW-MX1A-11NW")
      (description "SWITCH PUSH SPST-NO 0.01A 12V")
      (fields (field (name "MANUFACTURER") "Cherry"))
      (libsource (lib "Schlib1") (part "SW-CHERRY-MX"))
    )
    (comp (ref "SW67")
      (value "B3U-1000P")
      (footprint "SW-B3U-1000P")
      (description "SWITCH TACTILE SPST-NO 0.05A 12V")
      (fields (field (name "MANUFACTURER") "Omron"))
      (libsource (lib "Schlib1") (part "SW-B3U-1000P"))
    )
    (comp (ref "U1")
      (value "ATMEGA32U4-AUR")
      (footprint "TQFP44-ATMEL")
      (description "IC MCU 8BIT 32KB FLASH 44TQFP")
      (fields (field (name "MANUFACTURER") "Microchip"))
      (libsource (lib "Schlib1") (part "ATMEGA32U4-AUR"))
    )
    (comp (ref "Y1")
      (value "16MHZ")
      (footprint "XTAL_3.2mmx2.5mm")
      (description "=Reference")
      (fields
        (field (name "MANUFACTURER") "Epson")
        (field (name "MANUFACTURER PART NUMBER") "FA-238 16.0000MB-C3")
      )
      (libsource (lib "Altium_Library") (part "XTAL_3.2mmx2.5mm"))
    )
  )
  (nets
    (net (code "1") (name "+5V0") (class "Default")
      (node (ref "C4") (pin "2") (pinfunction "2_2") (pintype "passive"))
      (node (ref "C5") (pin "2") (pinfunction "2_2") (pintype "passive"))
      (node (ref "C6") (pin "2") (pinfunction "2_2") (pintype "passive"))
      (node (ref "C7") (pin "2") (pinfunction "2_2") (pintype "passive"))
      (node (ref "C8") (pin "2") (pinfunction "2_2") (pintype "passive"))
      (node (ref "C9") (pin "2") (pinfunction "2_2") (pintype "passive"))
      (node (ref "J1") (pin "1") (pinfunction "VBUS_1") (pintype "passive"))
      (node (ref "P1") (pin "1") (pintype "passive"))
      (node (ref "R1") (pin "2") (pinfunction "2_2") (pintype "passive"))
      (node (ref "U1") (pin "14") (pinfunction "VCC_14") (pintype "passive"))
      (node (ref "U1") (pin "2") (pinfunction "UVcc_2") (pintype "passive"))
      (node (ref "U1") (pin "24") (pinfunction "AVCC_24") (pintype "passive"))
      (node (ref "U1") (pin "34") (pinfunction "VCC_34") (pintype "passive"))
      (node (ref "U1") (pin "44") (pinfunction "AVCC_44") (pintype "passive"))
      (node (ref "U1") (pin "7") (pinfunction "VBus_7") (pintype "passive"))
    )
    (net (code "2") (name "/BLINKY1") (class "Default")
      (node (ref "R4") (pin "1") (pinfunction "1_1") (pintype "passive"))
      (node (ref "U1") (pin "9") (pinfunction "PB1_(PCINT1/SCLK)_9") (pintype "passive"))
    )
    (net (code "3") (name "/BLINKY2") (class "Default")
      (node (ref "R5") (pin "1") (pinfunction "1_1") (pintype "passive"))
      (node (ref "U1") (pin "10") (pinfunction "PB2_(PDI/PCINT2/MOSI)_10") (pintype "passive"))
    )
    (net (code "4") (name "/BLINKY3") (class "Default")
      (node (ref "R6") (pin "1") (pinfunction "1_1") (pintype "passive"))
      (node (ref "U1") (pin "11") (pinfunction "PB3_(PDO/PCINT3/MISO)_11") (pintype "passive"))
    )
    (net (code "5") (name "/COL1") (class "Default")
      (node (ref "D1") (pin "1") (pinfunction "K_1") (pintype "passive"))
      (node (ref "D17") (pin "1") (pinfunction "K_1") (pintype "passive"))
      (node (ref "D32") (pin "1") (pinfunction "K_1") (pintype "passive"))
      (node (ref "U1") (pin "41") (pinfunction "PF0_(ADC0)_41") (pintype "passive"))
    )
    (net (code "6") (name "/COL2") (class "Default")
      (node (ref "D18") (pin "1") (pinfunction "K_1") (pintype "passive"))
      (node (ref "D2") (pin "1") (pinfunction "K_1") (pintype "passive"))
      (node (ref "D33") (pin "1") (pinfunction "K_1") (pintype "passive"))
      (node (ref "D46") (pin "1") (pinfunction "K_1") (pintype "passive"))
      (node (ref "D60") (pin "1") (pinfunction "K_1") (pintype "passive"))
      (node (ref "U1") (pin "40") (pinfunction "PF1_(ADC1)_40") (pintype "passive"))
    )
    (net (code "7") (name "/COL3") (class "Default")
      (node (ref "D19") (pin "1") (pinfunction "K_1") (pintype "passive"))
      (node (ref "D3") (pin "1") (pinfunction "K_1") (pintype "passive"))
      (node (ref "D34") (pin "1") (pinfunction "K_1") (pintype "passive"))
      (node (ref "D47") (pin "1") (pinfunction "K_1") (pintype "passive"))
      (node (ref "D61") (pin "1") (pinfunction "K_1") (pintype "passive"))
      (node (ref "U1") (pin "39") (pinfunction "PF4_(ADC4/TCK)_39") (pintype "passive"))
    )
    (net (code "8") (name "/COL4") (class "Default")
      (node (ref "D20") (pin "1") (pinfunction "K_1") (pintype "passive"))
      (node (ref "D35") (pin "1") (pinfunction "K_1") (pintype "passive"))
      (node (ref "D4") (pin "1") (pinfunction "K_1") (pintype "passive"))
      (node (ref "D48") (pin "1") (pinfunction "K_1") (pintype "passive"))
      (node (ref "D62") (pin "1") (pinfunction "K_1") (pintype "passive"))
      (node (ref "U1") (pin "38") (pinfunction "PF5_(ADC5/TMS))_38") (pintype "passive"))
    )
    (net (code "9") (name "/COL5") (class "Default")
      (node (ref "D21") (pin "1") (pinfunction "K_1") (pintype "passive"))
      (node (ref "D36") (pin "1") (pinfunction "K_1") (pintype "passive"))
      (node (ref "D49") (pin "1") (pinfunction "K_1") (pintype "passive"))
      (node (ref "D5") (pin "1") (pinfunction "K_1") (pintype "passive"))
      (node (ref "U1") (pin "37") (pinfunction "PF6_(ADC6/TDO_37") (pintype "passive"))
    )
    (net (code "10") (name "/COL6") (class "Default")
      (node (ref "D22") (pin "1") (pinfunction "K_1") (pintype "passive"))
      (node (ref "D37") (pin "1") (pinfunction "K_1") (pintype "passive"))
      (node (ref "D50") (pin "1") (pinfunction "K_1") (pintype "passive"))
      (node (ref "D6") (pin "1") (pinfunction "K_1") (pintype "passive"))
      (node (ref "D63") (pin "1") (pinfunction "K_1") (pintype "passive"))
      (node (ref "U1") (pin "36") (pinfunction "PF7_(ADC7/TDI)_36") (pintype "passive"))
    )
    (net (code "11") (name "/COL7") (class "Default")
      (node (ref "D23") (pin "1") (pinfunction "K_1") (pintype "passive"))
      (node (ref "D38") (pin "1") (pinfunction "K_1") (pintype "passive"))
      (node (ref "D51") (pin "1") (pinfunction "K_1") (pintype "passive"))
      (node (ref "D7") (pin "1") (pinfunction "K_1") (pintype "passive"))
      (node (ref "U1") (pin "33") (pinfunction "PE2_(~{HWB})_33") (pintype "passive"))
    )
    (net (code "12") (name "/COL8") (class "Default")
      (node (ref "D24") (pin "1") (pinfunction "K_1") (pintype "passive"))
      (node (ref "D39") (pin "1") (pinfunction "K_1") (pintype "passive"))
      (node (ref "D52") (pin "1") (pinfunction "K_1") (pintype "passive"))
      (node (ref "D64") (pin "1") (pinfunction "K_1") (pintype "passive"))
      (node (ref "D8") (pin "1") (pinfunction "K_1") (pintype "passive"))
      (node (ref "U1") (pin "32") (pinfunction "PC7_(ICP3/CLK0/~{OC4A})_32") (pintype "passive"))
    )
    (net (code "13") (name "/COL9") (class "Default")
      (node (ref "D25") (pin "1") (pinfunction "K_1") (pintype "passive"))
      (node (ref "D40") (pin "1") (pinfunction "K_1") (pintype "passive"))
      (node (ref "D53") (pin "1") (pinfunction "K_1") (pintype "passive"))
      (node (ref "D9") (pin "1") (pinfunction "K_1") (pintype "passive"))
      (node (ref "U1") (pin "25") (pinfunction "PD4_(ICP1/ADC8)_25") (pintype "passive"))
    )
    (net (code "14") (name "/COL10") (class "Default")
      (node (ref "D10") (pin "1") (pinfunction "K_1") (pintype "passive"))
      (node (ref "D26") (pin "1") (pinfunction "K_1") (pintype "passive"))
      (node (ref "D41") (pin "1") (pinfunction "K_1") (pintype "passive"))
      (node (ref "D54") (pin "1") (pinfunction "K_1") (pintype "passive"))
      (node (ref "U1") (pin "26") (pinfunction "PD6_(T1/~{OC4D}/ADC9)_26") (pintype "passive"))
    )
    (net (code "15") (name "/COL11") (class "Default")
      (node (ref "D11") (pin "1") (pinfunction "K_1") (pintype "passive"))
      (node (ref "D27") (pin "1") (pinfunction "K_1") (pintype "passive"))
      (node (ref "D42") (pin "1") (pinfunction "K_1") (pintype "passive"))
      (node (ref "D55") (pin "1") (pinfunction "K_1") (pintype "passive"))
      (node (ref "D65") (pin "1") (pinfunction "K_1") (pintype "passive"))
      (node (ref "U1") (pin "27") (pinfunction "PD7_(T0/OC4D/ADC10)_27") (pintype "passive"))
    )
    (net (code "16") (name "/COL12") (class "Default")
      (node (ref "D12") (pin "1") (pinfunction "K_1") (pintype "passive"))
      (node (ref "D28") (pin "1") (pinfunction "K_1") (pintype "passive"))
      (node (ref "D43") (pin "1") (pinfunction "K_1") (pintype "passive"))
      (node (ref "D56") (pin "1") (pinfunction "K_1") (pintype "passive"))
      (node (ref "U1") (pin "28") (pinfunction "PB4_(PCINT4/ADC11)_28") (pintype "passive"))
    )
    (net (code "17") (name "/COL13") (class "Default")
      (node (ref "D13") (pin "1") (pinfunction "K_1") (pintype "passive"))
      (node (ref "D29") (pin "1") (pinfunction "K_1") (pintype "passive"))
      (node (ref "D44") (pin "1") (pinfunction "K_1") (pintype "passive"))
      (node (ref "D57") (pin "1") (pinfunction "K_1") (pintype "passive"))
      (node (ref "U1") (pin "29") (pinfunction "PB5_(PCINT5/OC1A/~{OC4B}/ADC12)_29") (pintype "passive"))
    )
    (net (code "18") (name "/COL14") (class "Default")
      (node (ref "D14") (pin "1") (pinfunction "K_1") (pintype "passive"))
      (node (ref "D30") (pin "1") (pinfunction "K_1") (pintype "passive"))
      (node (ref "D45") (pin "1") (pinfunction "K_1") (pintype "passive"))
      (node (ref "D58") (pin "1") (pinfunction "K_1") (pintype "passive"))
      (node (ref "U1") (pin "30") (pinfunction "PB6_(PCINT6/OC1B/OC4B/ADC13)_30") (pintype "passive"))
    )
    (net (code "19") (name "/COL15") (class "Default")
      (node (ref "D15") (pin "1") (pinfunction "K_1") (pintype "passive"))
      (node (ref "D16") (pin "1") (pinfunction "K_1") (pintype "passive"))
      (node (ref "D31") (pin "1") (pinfunction "K_1") (pintype "passive"))
      (node (ref "D59") (pin "1") (pinfunction "K_1") (pintype "passive"))
      (node (ref "D66") (pin "1") (pinfunction "K_1") (pintype "passive"))
      (node (ref "U1") (pin "31") (pinfunction "PC6_(OC3A/OC4A)_31") (pintype "passive"))
    )
    (net (code "20") (name "/D+") (class "Default")
      (node (ref "R3") (pin "2") (pinfunction "2_2") (pintype "passive"))
      (node (ref "U1") (pin "4") (pinfunction "D+_4") (pintype "passive"))
    )
    (net (code "21") (name "/D-") (class "Default")
      (node (ref "R2") (pin "2") (pinfunction "2_2") (pintype "passive"))
      (node (ref "U1") (pin "3") (pinfunction "D-_3") (pintype "passive"))
    )
    (net (code "22") (name "/ROW1") (class "Default")
      (node (ref "SW60") (pin "2") (pinfunction "2_2") (pintype "passive"))
      (node (ref "SW61") (pin "2") (pinfunction "2_2") (pintype "passive"))
      (node (ref "SW62") (pin "2") (pinfunction "2_2") (pintype "passive"))
      (node (ref "SW63") (pin "2") (pinfunction "2_2") (pintype "passive"))
      (node (ref "SW64") (pin "2") (pinfunction "2_2") (pintype "passive"))
      (node (ref "SW65") (pin "2") (pinfunction "2_2") (pintype "passive"))
      (node (ref "SW66") (pin "2") (pinfunction "2_2") (pintype "passive"))
      (node (ref "U1") (pin "22") (pinfunction "PD5_(XCK1/~{CTS})_22") (pintype "passive"))
    )
    (net (code "23") (name "/ROW2") (class "Default")
      (node (ref "SW46") (pin "2") (pinfunction "2_2") (pintype "passive"))
      (node (ref "SW47") (pin "2") (pinfunction "2_2") (pintype "passive"))
      (node (ref "SW48") (pin "2") (pinfunction "2_2") (pintype "passive"))
      (node (ref "SW49") (pin "2") (pinfunction "2_2") (pintype "passive"))
      (node (ref "SW50") (pin "2") (pinfunction "2_2") (pintype "passive"))
      (node (ref "SW51") (pin "2") (pinfunction "2_2") (pintype "passive"))
      (node (ref "SW52") (pin "2") (pinfunction "2_2") (pintype "passive"))
      (node (ref "SW53") (pin "2") (pinfunction "2_2") (pintype "passive"))
      (node (ref "SW54") (pin "2") (pinfunction "2_2") (pintype "passive"))
      (node (ref "SW55") (pin "2") (pinfunction "2_2") (pintype "passive"))
      (node (ref "SW56") (pin "2") (pinfunction "2_2") (pintype "passive"))
      (node (ref "SW57") (pin "2") (pinfunction "2_2") (pintype "passive"))
      (node (ref "SW58") (pin "2") (pinfunction "2_2") (pintype "passive"))
      (node (ref "SW59") (pin "2") (pinfunction "2_2") (pintype "passive"))
      (node (ref "U1") (pin "21") (pinfunction "PD3_(TXD1/INT3)_21") (pintype "passive"))
    )
    (net (code "24") (name "/ROW3") (class "Default")
      (node (ref "SW32") (pin "2") (pinfunction "2_2") (pintype "passive"))
      (node (ref "SW33") (pin "2") (pinfunction "2_2") (pintype "passive"))
      (node (ref "SW34") (pin "2") (pinfunction "2_2") (pintype "passive"))
      (node (ref "SW35") (pin "2") (pinfunction "2_2") (pintype "passive"))
      (node (ref "SW36") (pin "2") (pinfunction "2_2") (pintype "passive"))
      (node (ref "SW37") (pin "2") (pinfunction "2_2") (pintype "passive"))
      (node (ref "SW38") (pin "2") (pinfunction "2_2") (pintype "passive"))
      (node (ref "SW39") (pin "2") (pinfunction "2_2") (pintype "passive"))
      (node (ref "SW40") (pin "2") (pinfunction "2_2") (pintype "passive"))
      (node (ref "SW41") (pin "2") (pinfunction "2_2") (pintype "passive"))
      (node (ref "SW42") (pin "2") (pinfunction "2_2") (pintype "passive"))
      (node (ref "SW43") (pin "2") (pinfunction "2_2") (pintype "passive"))
      (node (ref "SW44") (pin "2") (pinfunction "2_2") (pintype "passive"))
      (node (ref "SW45") (pin "2") (pinfunction "2_2") (pintype "passive"))
      (node (ref "U1") (pin "20") (pinfunction "PD2_(RXD1/INT2)_20") (pintype "passive"))
    )
    (net (code "25") (name "/ROW4") (class "Default")
      (node (ref "SW16") (pin "2") (pinfunction "2_2") (pintype "passive"))
      (node (ref "SW17") (pin "2") (pinfunction "2_2") (pintype "passive"))
      (node (ref "SW18") (pin "2") (pinfunction "2_2") (pintype "passive"))
      (node (ref "SW19") (pin "2") (pinfunction "2_2") (pintype "passive"))
      (node (ref "SW20") (pin "2") (pinfunction "2_2") (pintype "passive"))
      (node (ref "SW21") (pin "2") (pinfunction "2_2") (pintype "passive"))
      (node (ref "SW22") (pin "2") (pinfunction "2_2") (pintype "passive"))
      (node (ref "SW23") (pin "2") (pinfunction "2_2") (pintype "passive"))
      (node (ref "SW24") (pin "2") (pinfunction "2_2") (pintype "passive"))
      (node (ref "SW25") (pin "2") (pinfunction "2_2") (pintype "passive"))
      (node (ref "SW26") (pin "2") (pinfunction "2_2") (pintype "passive"))
      (node (ref "SW27") (pin "2") (pinfunction "2_2") (pintype "passive"))
      (node (ref "SW28") (pin "2") (pinfunction "2_2") (pintype "passive"))
      (node (ref "SW29") (pin "2") (pinfunction "2_2") (pintype "passive"))
      (node (ref "SW30") (pin "2") (pinfunction "2_2") (pintype "passive"))
      (node (ref "SW31") (pin "2") (pinfunction "2_2") (pintype "passive"))
      (node (ref "U1") (pin "19") (pinfunction "PD1_(SDA/INT1)_19") (pintype "passive"))
    )
    (net (code "26") (name "/ROW5") (class "Default")
      (node (ref "SW1") (pin "2") (pinfunction "2_2") (pintype "passive"))
      (node (ref "SW10") (pin "2") (pinfunction "2_2") (pintype "passive"))
      (node (ref "SW11") (pin "2") (pinfunction "2_2") (pintype "passive"))
      (node (ref "SW12") (pin "2") (pinfunction "2_2") (pintype "passive"))
      (node (ref "SW13") (pin "2") (pinfunction "2_2") (pintype "passive"))
      (node (ref "SW14") (pin "2") (pinfunction "2_2") (pintype "passive"))
      (node (ref "SW15") (pin "2") (pinfunction "2_2") (pintype "passive"))
      (node (ref "SW2") (pin "2") (pinfunction "2_2") (pintype "passive"))
      (node (ref "SW3") (pin "2") (pinfunction "2_2") (pintype "passive"))
      (node (ref "SW4") (pin "2") (pinfunction "2_2") (pintype "passive"))
      (node (ref "SW5") (pin "2") (pinfunction "2_2") (pintype "passive"))
      (node (ref "SW6") (pin "2") (pinfunction "2_2") (pintype "passive"))
      (node (ref "SW7") (pin "2") (pinfunction "2_2") (pintype "passive"))
      (node (ref "SW8") (pin "2") (pinfunction "2_2") (pintype "passive"))
      (node (ref "SW9") (pin "2") (pinfunction "2_2") (pintype "passive"))
      (node (ref "U1") (pin "18") (pinfunction "PD0_(OC0B/SCL/INT0)_18") (pintype "passive"))
    )
    (net (code "27") (name "GND") (class "Default")
      (node (ref "C1") (pin "1") (pinfunction "1_1") (pintype "passive"))
      (node (ref "C2") (pin "1") (pinfunction "1_1") (pintype "passive"))
      (node (ref "C3") (pin "1") (pinfunction "1_1") (pintype "passive"))
      (node (ref "C4") (pin "1") (pinfunction "1_1") (pintype "passive"))
      (node (ref "C5") (pin "1") (pinfunction "1_1") (pintype "passive"))
      (node (ref "C6") (pin "1") (pinfunction "1_1") (pintype "passive"))
      (node (ref "C7") (pin "1") (pinfunction "1_1") (pintype "passive"))
      (node (ref "C8") (pin "1") (pinfunction "1_1") (pintype "passive"))
      (node (ref "C9") (pin "1") (pinfunction "1_1") (pintype "passive"))
      (node (ref "D67") (pin "1") (pinfunction "K_1") (pintype "passive"))
      (node (ref "D68") (pin "1") (pinfunction "K_1") (pintype "passive"))
      (node (ref "D69") (pin "1") (pinfunction "K_1") (pintype "passive"))
      (node (ref "J1") (pin "5") (pinfunction "GND_5") (pintype "passive"))
      (node (ref "J1") (pin "6") (pinfunction "SHIELD_6") (pintype "passive"))
      (node (ref "P3") (pin "1") (pintype "passive"))
      (node (ref "SW67") (pin "1") (pinfunction "1_1") (pintype "passive"))
      (node (ref "U1") (pin "15") (pinfunction "GND_15") (pintype "passive"))
      (node (ref "U1") (pin "23") (pinfunction "GND_23") (pintype "passive"))
      (node (ref "U1") (pin "35") (pinfunction "GND_35") (pintype "passive"))
      (node (ref "U1") (pin "43") (pinfunction "GND_43") (pintype "passive"))
      (node (ref "U1") (pin "5") (pinfunction "UGnd_5") (pintype "passive"))
      (node (ref "Y1") (pin "2") (pintype "passive"))
      (node (ref "Y1") (pin "4") (pintype "passive"))
    )
    (net (code "28") (name "Net-(D1-A)") (class "Default")
      (node (ref "D1") (pin "2") (pinfunction "A_2") (pintype "passive"))
      (node (ref "SW1") (pin "1") (pinfunction "1_1") (pintype "passive"))
    )
    (net (code "29") (name "Net-(D2-A)") (class "Default")
      (node (ref "D2") (pin "2") (pinfunction "A_2") (pintype "passive"))
      (node (ref "SW2") (pin "1") (pinfunction "1_1") (pintype "passive"))
    )
    (net (code "30") (name "Net-(D3-A)") (class "Default")
      (node (ref "D3") (pin "2") (pinfunction "A_2") (pintype "passive"))
      (node (ref "SW3") (pin "1") (pinfunction "1_1") (pintype "passive"))
    )
    (net (code "31") (name "Net-(D4-A)") (class "Default")
      (node (ref "D4") (pin "2") (pinfunction "A_2") (pintype "passive"))
      (node (ref "SW4") (pin "1") (pinfunction "1_1") (pintype "passive"))
    )
    (net (code "32") (name "Net-(D5-A)") (class "Default")
      (node (ref "D5") (pin "2") (pinfunction "A_2") (pintype "passive"))
      (node (ref "SW5") (pin "1") (pinfunction "1_1") (pintype "passive"))
    )
    (net (code "33") (name "Net-(D6-A)") (class "Default")
      (node (ref "D6") (pin "2") (pinfunction "A_2") (pintype "passive"))
      (node (ref "SW6") (pin "1") (pinfunction "1_1") (pintype "passive"))
    )
    (net (code "34") (name "Net-(D7-A)") (class "Default")
      (node (ref "D7") (pin "2") (pinfunction "A_2") (pintype "passive"))
      (node (ref "SW7") (pin "1") (pinfunction "1_1") (pintype "passive"))
    )
    (net (code "35") (name "Net-(D8-A)") (class "Default")
      (node (ref "D8") (pin "2") (pinfunction "A_2") (pintype "passive"))
      (node (ref "SW8") (pin "1") (pinfunction "1_1") (pintype "passive"))
    )
    (net (code "36") (name "Net-(D9-A)") (class "Default")
      (node (ref "D9") (pin "2") (pinfunction "A_2") (pintype "passive"))
      (node (ref "SW9") (pin "1") (pinfunction "1_1") (pintype "passive"))
    )
    (net (code "37") (name "Net-(D10-A)") (class "Default")
      (node (ref "D10") (pin "2") (pinfunction "A_2") (pintype "passive"))
      (node (ref "SW10") (pin "1") (pinfunction "1_1") (pintype "passive"))
    )
    (net (code "38") (name "Net-(D11-A)") (class "Default")
      (node (ref "D11") (pin "2") (pinfunction "A_2") (pintype "passive"))
      (node (ref "SW11") (pin "1") (pinfunction "1_1") (pintype "passive"))
    )
    (net (code "39") (name "Net-(D12-A)") (class "Default")
      (node (ref "D12") (pin "2") (pinfunction "A_2") (pintype "passive"))
      (node (ref "SW12") (pin "1") (pinfunction "1_1") (pintype "passive"))
    )
    (net (code "40") (name "Net-(D13-A)") (class "Default")
      (node (ref "D13") (pin "2") (pinfunction "A_2") (pintype "passive"))
      (node (ref "SW13") (pin "1") (pinfunction "1_1") (pintype "passive"))
    )
    (net (code "41") (name "Net-(D14-A)") (class "Default")
      (node (ref "D14") (pin "2") (pinfunction "A_2") (pintype "passive"))
      (node (ref "SW14") (pin "1") (pinfunction "1_1") (pintype "passive"))
    )
    (net (code "42") (name "Net-(D15-A)") (class "Default")
      (node (ref "D15") (pin "2") (pinfunction "A_2") (pintype "passive"))
      (node (ref "SW15") (pin "1") (pinfunction "1_1") (pintype "passive"))
    )
    (net (code "43") (name "Net-(D16-A)") (class "Default")
      (node (ref "D16") (pin "2") (pinfunction "A_2") (pintype "passive"))
      (node (ref "SW16") (pin "1") (pinfunction "1_1") (pintype "passive"))
    )
    (net (code "44") (name "Net-(D17-A)") (class "Default")
      (node (ref "D17") (pin "2") (pinfunction "A_2") (pintype "passive"))
      (node (ref "SW17") (pin "1") (pinfunction "1_1") (pintype "passive"))
    )
    (net (code "45") (name "Net-(D18-A)") (class "Default")
      (node (ref "D18") (pin "2") (pinfunction "A_2") (pintype "passive"))
      (node (ref "SW18") (pin "1") (pinfunction "1_1") (pintype "passive"))
    )
    (net (code "46") (name "Net-(D19-A)") (class "Default")
      (node (ref "D19") (pin "2") (pinfunction "A_2") (pintype "passive"))
      (node (ref "SW19") (pin "1") (pinfunction "1_1") (pintype "passive"))
    )
    (net (code "47") (name "Net-(D20-A)") (class "Default")
      (node (ref "D20") (pin "2") (pinfunction "A_2") (pintype "passive"))
      (node (ref "SW20") (pin "1") (pinfunction "1_1") (pintype "passive"))
    )
    (net (code "48") (name "Net-(D21-A)") (class "Default")
      (node (ref "D21") (pin "2") (pinfunction "A_2") (pintype "passive"))
      (node (ref "SW21") (pin "1") (pinfunction "1_1") (pintype "passive"))
    )
    (net (code "49") (name "Net-(D22-A)") (class "Default")
      (node (ref "D22") (pin "2") (pinfunction "A_2") (pintype "passive"))
      (node (ref "SW22") (pin "1") (pinfunction "1_1") (pintype "passive"))
    )
    (net (code "50") (name "Net-(D23-A)") (class "Default")
      (node (ref "D23") (pin "2") (pinfunction "A_2") (pintype "passive"))
      (node (ref "SW23") (pin "1") (pinfunction "1_1") (pintype "passive"))
    )
    (net (code "51") (name "Net-(D24-A)") (class "Default")
      (node (ref "D24") (pin "2") (pinfunction "A_2") (pintype "passive"))
      (node (ref "SW24") (pin "1") (pinfunction "1_1") (pintype "passive"))
    )
    (net (code "52") (name "Net-(D25-A)") (class "Default")
      (node (ref "D25") (pin "2") (pinfunction "A_2") (pintype "passive"))
      (node (ref "SW25") (pin "1") (pinfunction "1_1") (pintype "passive"))
    )
    (net (code "53") (name "Net-(D26-A)") (class "Default")
      (node (ref "D26") (pin "2") (pinfunction "A_2") (pintype "passive"))
      (node (ref "SW26") (pin "1") (pinfunction "1_1") (pintype "passive"))
    )
    (net (code "54") (name "Net-(D27-A)") (class "Default")
      (node (ref "D27") (pin "2") (pinfunction "A_2") (pintype "passive"))
      (node (ref "SW27") (pin "1") (pinfunction "1_1") (pintype "passive"))
    )
    (net (code "55") (name "Net-(D28-A)") (class "Default")
      (node (ref "D28") (pin "2") (pinfunction "A_2") (pintype "passive"))
      (node (ref "SW28") (pin "1") (pinfunction "1_1") (pintype "passive"))
    )
    (net (code "56") (name "Net-(D29-A)") (class "Default")
      (node (ref "D29") (pin "2") (pinfunction "A_2") (pintype "passive"))
      (node (ref "SW29") (pin "1") (pinfunction "1_1") (pintype "passive"))
    )
    (net (code "57") (name "Net-(D30-A)") (class "Default")
      (node (ref "D30") (pin "2") (pinfunction "A_2") (pintype "passive"))
      (node (ref "SW30") (pin "1") (pinfunction "1_1") (pintype "passive"))
    )
    (net (code "58") (name "Net-(D31-A)") (class "Default")
      (node (ref "D31") (pin "2") (pinfunction "A_2") (pintype "passive"))
      (node (ref "SW31") (pin "1") (pinfunction "1_1") (pintype "passive"))
    )
    (net (code "59") (name "Net-(D32-A)") (class "Default")
      (node (ref "D32") (pin "2") (pinfunction "A_2") (pintype "passive"))
      (node (ref "SW32") (pin "1") (pinfunction "1_1") (pintype "passive"))
    )
    (net (code "60") (name "Net-(D33-A)") (class "Default")
      (node (ref "D33") (pin "2") (pinfunction "A_2") (pintype "passive"))
      (node (ref "SW33") (pin "1") (pinfunction "1_1") (pintype "passive"))
    )
    (net (code "61") (name "Net-(D34-A)") (class "Default")
      (node (ref "D34") (pin "2") (pinfunction "A_2") (pintype "passive"))
      (node (ref "SW34") (pin "1") (pinfunction "1_1") (pintype "passive"))
    )
    (net (code "62") (name "Net-(D35-A)") (class "Default")
      (node (ref "D35") (pin "2") (pinfunction "A_2") (pintype "passive"))
      (node (ref "SW35") (pin "1") (pinfunction "1_1") (pintype "passive"))
    )
    (net (code "63") (name "Net-(D36-A)") (class "Default")
      (node (ref "D36") (pin "2") (pinfunction "A_2") (pintype "passive"))
      (node (ref "SW36") (pin "1") (pinfunction "1_1") (pintype "passive"))
    )
    (net (code "64") (name "Net-(D37-A)") (class "Default")
      (node (ref "D37") (pin "2") (pinfunction "A_2") (pintype "passive"))
      (node (ref "SW37") (pin "1") (pinfunction "1_1") (pintype "passive"))
    )
    (net (code "65") (name "Net-(D38-A)") (class "Default")
      (node (ref "D38") (pin "2") (pinfunction "A_2") (pintype "passive"))
      (node (ref "SW38") (pin "1") (pinfunction "1_1") (pintype "passive"))
    )
    (net (code "66") (name "Net-(D39-A)") (class "Default")
      (node (ref "D39") (pin "2") (pinfunction "A_2") (pintype "passive"))
      (node (ref "SW39") (pin "1") (pinfunction "1_1") (pintype "passive"))
    )
    (net (code "67") (name "Net-(D40-A)") (class "Default")
      (node (ref "D40") (pin "2") (pinfunction "A_2") (pintype "passive"))
      (node (ref "SW40") (pin "1") (pinfunction "1_1") (pintype "passive"))
    )
    (net (code "68") (name "Net-(D41-A)") (class "Default")
      (node (ref "D41") (pin "2") (pinfunction "A_2") (pintype "passive"))
      (node (ref "SW41") (pin "1") (pinfunction "1_1") (pintype "passive"))
    )
    (net (code "69") (name "Net-(D42-A)") (class "Default")
      (node (ref "D42") (pin "2") (pinfunction "A_2") (pintype "passive"))
      (node (ref "SW42") (pin "1") (pinfunction "1_1") (pintype "passive"))
    )
    (net (code "70") (name "Net-(D43-A)") (class "Default")
      (node (ref "D43") (pin "2") (pinfunction "A_2") (pintype "passive"))
      (node (ref "SW43") (pin "1") (pinfunction "1_1") (pintype "passive"))
    )
    (net (code "71") (name "Net-(D44-A)") (class "Default")
      (node (ref "D44") (pin "2") (pinfunction "A_2") (pintype "passive"))
      (node (ref "SW44") (pin "1") (pinfunction "1_1") (pintype "passive"))
    )
    (net (code "72") (name "Net-(D45-A)") (class "Default")
      (node (ref "D45") (pin "2") (pinfunction "A_2") (pintype "passive"))
      (node (ref "SW45") (pin "1") (pinfunction "1_1") (pintype "passive"))
    )
    (net (code "73") (name "Net-(D46-A)") (class "Default")
      (node (ref "D46") (pin "2") (pinfunction "A_2") (pintype "passive"))
      (node (ref "SW46") (pin "1") (pinfunction "1_1") (pintype "passive"))
    )
    (net (code "74") (name "Net-(D47-A)") (class "Default")
      (node (ref "D47") (pin "2") (pinfunction "A_2") (pintype "passive"))
      (node (ref "SW47") (pin "1") (pinfunction "1_1") (pintype "passive"))
    )
    (net (code "75") (name "Net-(D48-A)") (class "Default")
      (node (ref "D48") (pin "2") (pinfunction "A_2") (pintype "passive"))
      (node (ref "SW48") (pin "1") (pinfunction "1_1") (pintype "passive"))
    )
    (net (code "76") (name "Net-(D49-A)") (class "Default")
      (node (ref "D49") (pin "2") (pinfunction "A_2") (pintype "passive"))
      (node (ref "SW49") (pin "1") (pinfunction "1_1") (pintype "passive"))
    )
    (net (code "77") (name "Net-(D50-A)") (class "Default")
      (node (ref "D50") (pin "2") (pinfunction "A_2") (pintype "passive"))
      (node (ref "SW50") (pin "1") (pinfunction "1_1") (pintype "passive"))
    )
    (net (code "78") (name "Net-(D51-A)") (class "Default")
      (node (ref "D51") (pin "2") (pinfunction "A_2") (pintype "passive"))
      (node (ref "SW51") (pin "1") (pinfunction "1_1") (pintype "passive"))
    )
    (net (code "79") (name "Net-(D52-A)") (class "Default")
      (node (ref "D52") (pin "2") (pinfunction "A_2") (pintype "passive"))
      (node (ref "SW52") (pin "1") (pinfunction "1_1") (pintype "passive"))
    )
    (net (code "80") (name "Net-(D53-A)") (class "Default")
      (node (ref "D53") (pin "2") (pinfunction "A_2") (pintype "passive"))
      (node (ref "SW53") (pin "1") (pinfunction "1_1") (pintype "passive"))
    )
    (net (code "81") (name "Net-(D54-A)") (class "Default")
      (node (ref "D54") (pin "2") (pinfunction "A_2") (pintype "passive"))
      (node (ref "SW54") (pin "1") (pinfunction "1_1") (pintype "passive"))
    )
    (net (code "82") (name "Net-(D55-A)") (class "Default")
      (node (ref "D55") (pin "2") (pinfunction "A_2") (pintype "passive"))
      (node (ref "SW55") (pin "1") (pinfunction "1_1") (pintype "passive"))
    )
    (net (code "83") (name "Net-(D56-A)") (class "Default")
      (node (ref "D56") (pin "2") (pinfunction "A_2") (pintype "passive"))
      (node (ref "SW56") (pin "1") (pinfunction "1_1") (pintype "passive"))
    )
    (net (code "84") (name "Net-(D57-A)") (class "Default")
      (node (ref "D57") (pin "2") (pinfunction "A_2") (pintype "passive"))
      (node (ref "SW57") (pin "1") (pinfunction "1_1") (pintype "passive"))
    )
    (net (code "85") (name "Net-(D58-A)") (class "Default")
      (node (ref "D58") (pin "2") (pinfunction "A_2") (pintype "passive"))
      (node (ref "SW58") (pin "1") (pinfunction "1_1") (pintype "passive"))
    )
    (net (code "86") (name "Net-(D59-A)") (class "Default")
      (node (ref "D59") (pin "2") (pinfunction "A_2") (pintype "passive"))
      (node (ref "SW59") (pin "1") (pinfunction "1_1") (pintype "passive"))
    )
    (net (code "87") (name "Net-(D60-A)") (class "Default")
      (node (ref "D60") (pin "2") (pinfunction "A_2") (pintype "passive"))
      (node (ref "SW60") (pin "1") (pinfunction "1_1") (pintype "passive"))
    )
    (net (code "88") (name "Net-(D61-A)") (class "Default")
      (node (ref "D61") (pin "2") (pinfunction "A_2") (pintype "passive"))
      (node (ref "SW61") (pin "1") (pinfunction "1_1") (pintype "passive"))
    )
    (net (code "89") (name "Net-(D62-A)") (class "Default")
      (node (ref "D62") (pin "2") (pinfunction "A_2") (pintype "passive"))
      (node (ref "SW62") (pin "1") (pinfunction "1_1") (pintype "passive"))
    )
    (net (code "90") (name "Net-(D63-A)") (class "Default")
      (node (ref "D63") (pin "2") (pinfunction "A_2") (pintype "passive"))
      (node (ref "SW63") (pin "1") (pinfunction "1_1") (pintype "passive"))
    )
    (net (code "91") (name "Net-(D64-A)") (class "Default")
      (node (ref "D64") (pin "2") (pinfunction "A_2") (pintype "passive"))
      (node (ref "SW64") (pin "1") (pinfunction "1_1") (pintype "passive"))
    )
    (net (code "92") (name "Net-(D65-A)") (class "Default")
      (node (ref "D65") (pin "2") (pinfunction "A_2") (pintype "passive"))
      (node (ref "SW65") (pin "1") (pinfunction "1_1") (pintype "passive"))
    )
    (net (code "93") (name "Net-(D66-A)") (class "Default")
      (node (ref "D66") (pin "2") (pinfunction "A_2") (pintype "passive"))
      (node (ref "SW66") (pin "1") (pinfunction "1_1") (pintype "passive"))
    )
    (net (code "94") (name "Net-(D67-A)") (class "Default")
      (node (ref "D67") (pin "2") (pinfunction "A_2") (pintype "passive"))
      (node (ref "R4") (pin "2") (pinfunction "2_2") (pintype "passive"))
    )
    (net (code "95") (name "Net-(D68-A)") (class "Default")
      (node (ref "D68") (pin "2") (pinfunction "A_2") (pintype "passive"))
      (node (ref "R5") (pin "2") (pinfunction "2_2") (pintype "passive"))
    )
    (net (code "96") (name "Net-(D69-A)") (class "Default")
      (node (ref "D69") (pin "2") (pinfunction "A_2") (pintype "passive"))
      (node (ref "R6") (pin "2") (pinfunction "2_2") (pintype "passive"))
    )
    (net (code "97") (name "Net-(J1-D+)") (class "Default")
      (node (ref "J1") (pin "3") (pinfunction "D+_3") (pintype "passive"))
      (node (ref "R3") (pin "1") (pinfunction "1_1") (pintype "passive"))
    )
    (net (code "98") (name "Net-(J1-D-)") (class "Default")
      (node (ref "J1") (pin "2") (pinfunction "D-_2") (pintype "passive"))
      (node (ref "R2") (pin "1") (pinfunction "1_1") (pintype "passive"))
    )
    (net (code "99") (name "Net-(U1-PE6_(INT.6{slash}AIN0))") (class "Default")
      (node (ref "P2") (pin "1") (pintype "passive"))
      (node (ref "U1") (pin "1") (pinfunction "PE6_(INT.6/AIN0)_1") (pintype "passive"))
    )
    (net (code "100") (name "Net-(U1-UCap)") (class "Default")
      (node (ref "C1") (pin "2") (pinfunction "2_2") (pintype "passive"))
      (node (ref "U1") (pin "6") (pinfunction "UCap_6") (pintype "passive"))
    )
    (net (code "101") (name "Net-(U1-XTAL1)") (class "Default")
      (node (ref "C3") (pin "2") (pinfunction "2_2") (pintype "passive"))
      (node (ref "U1") (pin "17") (pinfunction "XTAL1_17") (pintype "passive"))
      (node (ref "Y1") (pin "3") (pintype "passive"))
    )
    (net (code "102") (name "Net-(U1-XTAL2)") (class "Default")
      (node (ref "C2") (pin "2") (pinfunction "2_2") (pintype "passive"))
      (node (ref "U1") (pin "16") (pinfunction "XTAL2_16") (pintype "passive"))
      (node (ref "Y1") (pin "1") (pintype "passive"))
    )
    (net (code "103") (name "Net-(U1-~{RESET})") (class "Default")
      (node (ref "R1") (pin "1") (pinfunction "1_1") (pintype "passive"))
      (node (ref "SW67") (pin "2") (pinfunction "2_2") (pintype "passive"))
      (node (ref "U1") (pin "13") (pinfunction "~{RESET}_13") (pintype "passive"))
    )
    (net (code "104") (name "unconnected-(J1-ID-Pad4)") (class "Default")
      (node (ref "J1") (pin "4") (pinfunction "ID_4") (pintype "passive+no_connect"))
    )
    (net (code "105") (name "unconnected-(U1-AREF-Pad42)") (class "Default")
      (node (ref "U1") (pin "42") (pinfunction "AREF_42") (pintype "passive+no_connect"))
    )
    (net (code "106") (name "unconnected-(U1-PB0_(SS{slash}PCINT0)-Pad8)") (class "Default")
      (node (ref "U1") (pin "8") (pinfunction "PB0_(SS/PCINT0)_8") (pintype "passive+no_connect"))
    )
    (net (code "107") (name "unconnected-(U1-PB7_(PCINT7{slash}OC0A{slash}OC1C{slash}~{RTS})-Pad12)") (class "Default")
      (node (ref "U1") (pin "12") (pinfunction "PB7_(PCINT7/OC0A/OC1C/~{RTS})_12") (pintype "passive+no_connect"))
    )
  )
)
